# breakbeam-interface.net
KiCad netlist of a schematic drawn in Altium Designer
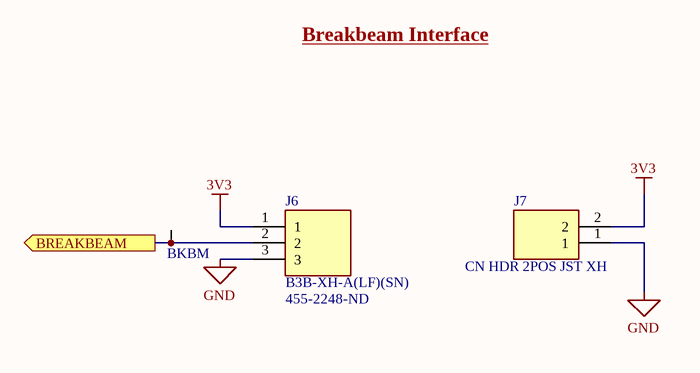
[diagram p0: breakbeam-interface.SchDoc]

(export (version "E")
  (design (tool "Eeschema 10.0.6"))
  (components
    (comp (ref "BKBM")
      (value "Test Point (Via)")
      (footprint "TP")
      (libsource (lib "IC_Library") (part "Test Point (Via)"))
    )
    (comp (ref "J6")
      (value "B3B-XH-A(LF)(SN)")
      (footprint "JST_B3B-XH-A(LF)(SN)")
      (description "Connector Header Through Hole 3 position 0.098 (2.50mm)")
      (fields
        (field (name "MF") "JST Sales")
        (field (name "SUPPLIER PART NUMBER 1") "455-2248-ND")
        (field (name "PART NUMBER") "CN HDR 3POS JST XH")
      )
      (libsource (lib "Connector_Library") (part "CN HDR 3POS JST XH"))
    )
    (comp (ref "J7")
      (value "CN HDR 2POS JST XH")
      (footprint "JST_B2B-XH-A(LF)(SN)")
      (description "Connector Header Through Hole 2 position 0.098 _2.50mm_\r\nJST XH")
      (fields (field (name "MP") "B2B-XH-A_LF__SN_") (field (name "MF") "JST Sales"))
      (libsource (lib "Connector_Library") (part "CN HDR 2POS JST XH"))
    )
  )
  (nets
    (net (code "1") (name "/BREAKBEAM") (class "Default")
      (node (ref "BKBM") (pin "1") (pinfunction "1_1") (pintype "passive"))
      (node (ref "J6") (pin "2") (pinfunction "2_2") (pintype "passive"))
    )
    (net (code "2") (name "3V3") (class "Default")
      (node (ref "J6") (pin "1") (pinfunction "1_1") (pintype "passive"))
      (node (ref "J7") (pin "2") (pinfunction "2_2") (pintype "passive"))
    )
    (net (code "3") (name "GND") (class "Default")
      (node (ref "J6") (pin "3") (pinfunction "3_3") (pintype "passive"))
      (node (ref "J7") (pin "1") (pinfunction "1_1") (pintype "passive"))
    )
  )
)
